# imu_68-v2.net
KiCad netlist of a schematic drawn in EAGLE
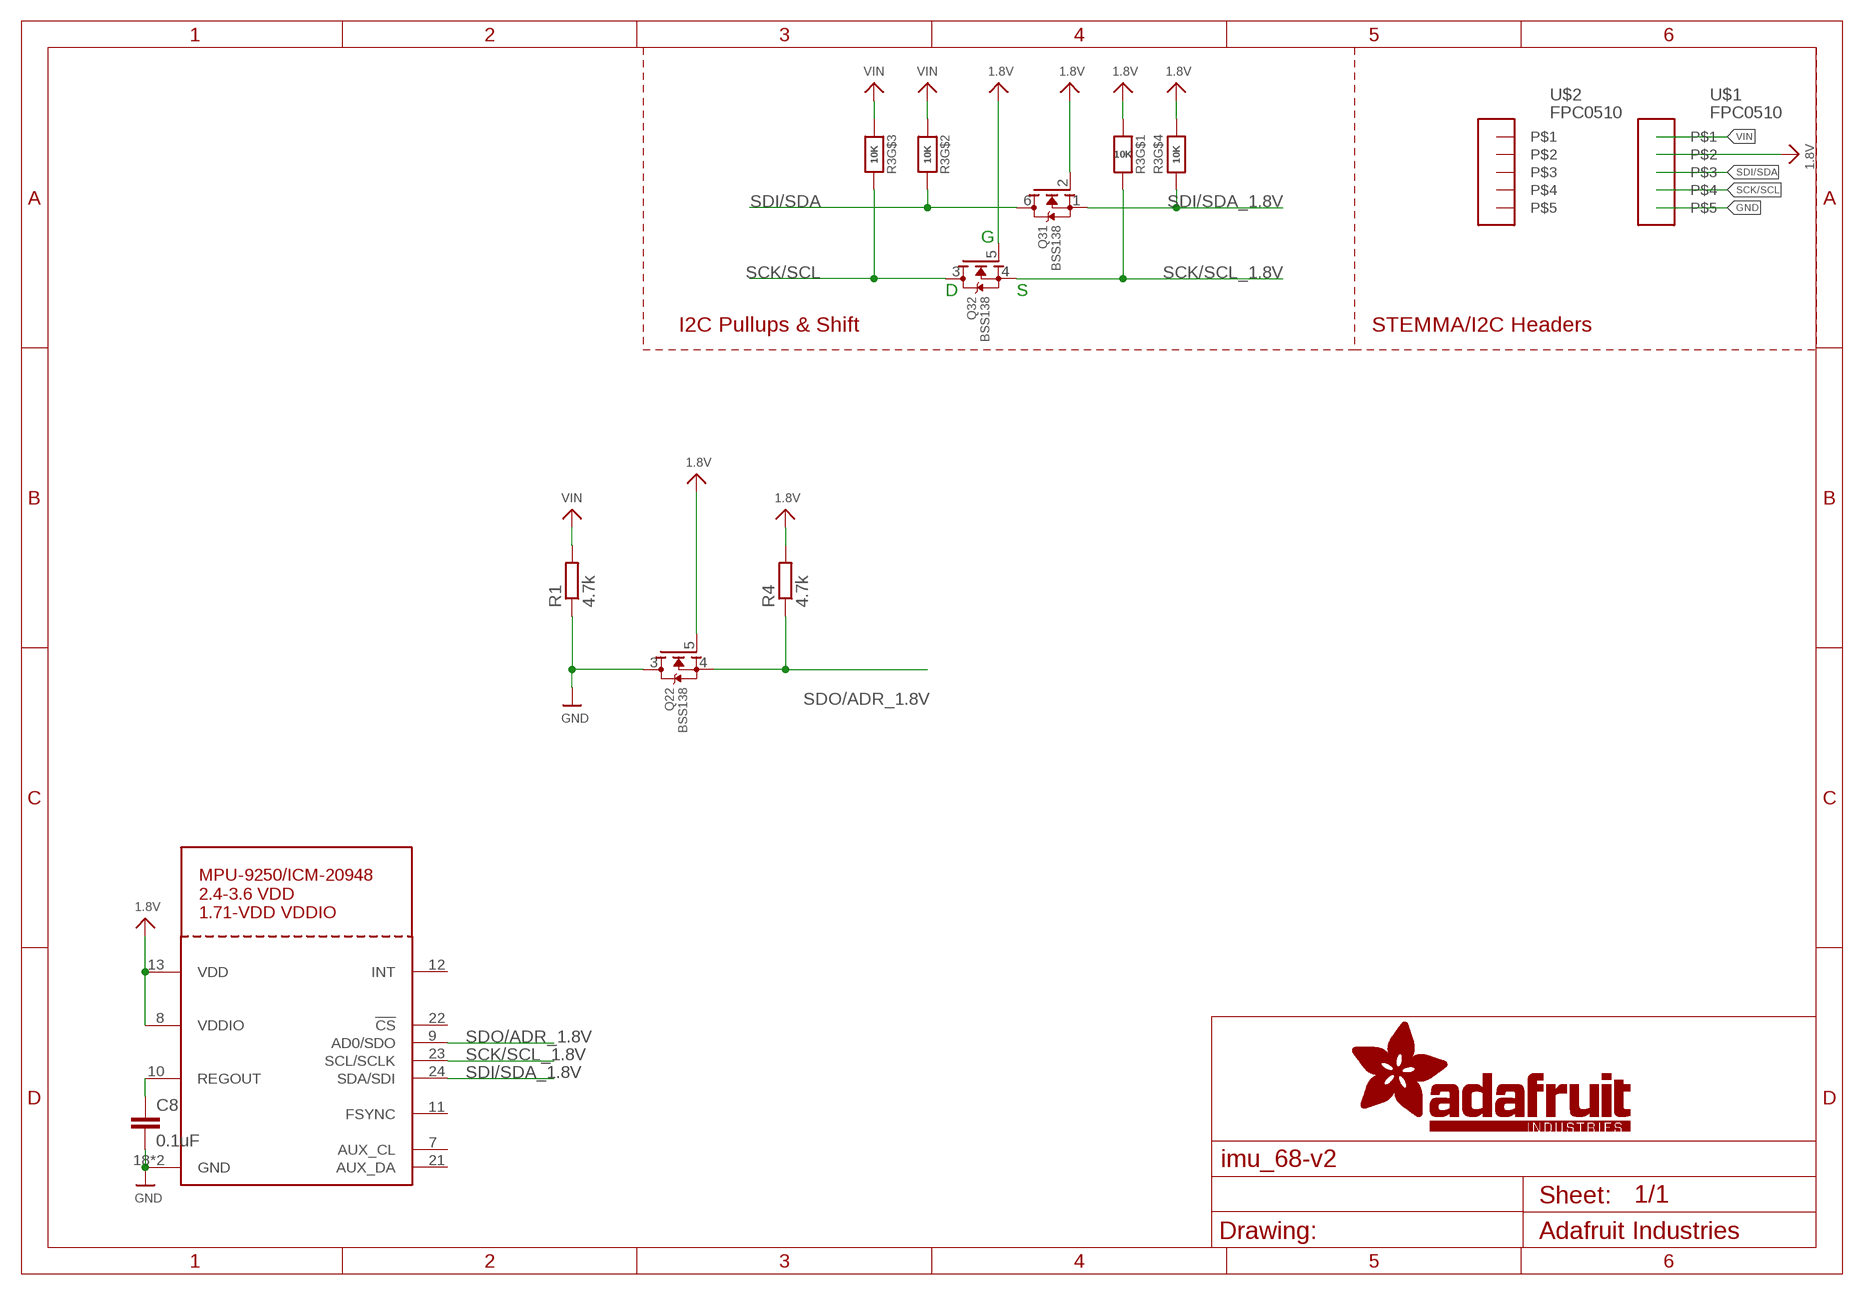
[diagram p0: schematic, sheet 1]

(export (version "E")
  (design (tool "Eeschema 10.0.6"))
  (components
    (comp (ref "C8")
      (value "0.1uF")
      (footprint "eagle-import:C0201")
      (libsource (lib "eagle-import") (part "C-EUC0201"))
    )
    (comp (ref "Q2")
      (value "BSS138")
      (footprint "eagle-import:SOT363")
      (libsource (lib "eagle-import") (part "MOSFET-N_DUAL"))
    )
    (comp (ref "Q3")
      (value "BSS138")
      (footprint "eagle-import:SOT363")
      (libsource (lib "eagle-import") (part "MOSFET-N_DUAL"))
    )
    (comp (ref "R1")
      (value "4.7k")
      (footprint "eagle-import:R0402")
      (libsource (lib "eagle-import") (part "R-EU_R0402"))
    )
    (comp (ref "R3")
      (value "10K")
      (footprint "eagle-import:RESPACK_4X0603")
      (libsource (lib "eagle-import") (part "RESISTOR_4PACK"))
    )
    (comp (ref "R4")
      (value "4.7k")
      (footprint "eagle-import:R0402")
      (libsource (lib "eagle-import") (part "R-EU_R0402"))
    )
    (comp (ref "U$1")
      (value "FPC0510")
      (footprint "eagle-import:FPC0510")
      (libsource (lib "eagle-import") (part "FPC0510"))
    )
    (comp (ref "U$2")
      (value "FPC0510")
      (footprint "eagle-import:FPC0510")
      (libsource (lib "eagle-import") (part "FPC0510"))
    )
    (comp (ref "U$21")
      (value "MPU-9250_ICM20948")
      (footprint "eagle-import:QFN24_3MM_NOEP")
      (libsource (lib "eagle-import") (part "MPU-9250_ICM20948"))
    )
  )
  (nets
    (net (code "1") (name "/SCK{slash}SCL_1.8V") (class "Default")
      (node (ref "Q3") (pin "4") (pinfunction "S_4") (pintype "bidirectional"))
      (node (ref "R3") (pin "1") (pinfunction "1_1") (pintype "passive"))
      (node (ref "U$21") (pin "23") (pinfunction "SCL/SCLK_23") (pintype "bidirectional"))
    )
    (net (code "2") (name "/SDI{slash}SDA_1.8V") (class "Default")
      (node (ref "Q3") (pin "1") (pinfunction "S_1") (pintype "bidirectional"))
      (node (ref "R3") (pin "5") (pinfunction "2_5") (pintype "passive"))
      (node (ref "U$21") (pin "24") (pinfunction "SDA/SDI_24") (pintype "bidirectional"))
    )
    (net (code "3") (name "/SDO{slash}ADR_1.8V") (class "Default")
      (node (ref "Q2") (pin "4") (pinfunction "S_4") (pintype "bidirectional"))
      (node (ref "R4") (pin "1") (pinfunction "1_1") (pintype "passive"))
      (node (ref "U$21") (pin "9") (pinfunction "AD0/SDO_9") (pintype "bidirectional"))
    )
    (net (code "4") (name "1.8V") (class "Default")
      (node (ref "Q2") (pin "5") (pinfunction "G_5") (pintype "bidirectional"))
      (node (ref "Q3") (pin "2") (pinfunction "G_2") (pintype "bidirectional"))
      (node (ref "Q3") (pin "5") (pinfunction "G_5") (pintype "bidirectional"))
      (node (ref "R3") (pin "4") (pinfunction "1_4") (pintype "passive"))
      (node (ref "R3") (pin "8") (pinfunction "2_8") (pintype "passive"))
      (node (ref "R4") (pin "2") (pinfunction "2_2") (pintype "passive"))
      (node (ref "U$1") (pin "P$2") (pinfunction "P$2_P$2") (pintype "bidirectional"))
      (node (ref "U$21") (pin "13") (pinfunction "VDD_13") (pintype "bidirectional"))
      (node (ref "U$21") (pin "8") (pinfunction "VDDIO_8") (pintype "bidirectional"))
    )
    (net (code "5") (name "GND") (class "Default")
      (node (ref "C8") (pin "2") (pinfunction "2_2") (pintype "passive"))
      (node (ref "Q2") (pin "3") (pinfunction "D_3") (pintype "bidirectional"))
      (node (ref "R1") (pin "1") (pinfunction "1_1") (pintype "passive"))
      (node (ref "U$1") (pin "P$5") (pinfunction "P$5_P$5") (pintype "bidirectional"))
      (node (ref "U$21") (pin "18") (pinfunction "GND_18") (pintype "bidirectional"))
      (node (ref "U$21") (pin "20") (pinfunction "GND_20") (pintype "bidirectional"))
    )
    (net (code "6") (name "Net-(U$21-REGOUT)") (class "Default")
      (node (ref "C8") (pin "1") (pinfunction "1_1") (pintype "passive"))
      (node (ref "U$21") (pin "10") (pinfunction "REGOUT_10") (pintype "bidirectional"))
    )
    (net (code "7") (name "SCK{slash}SCL") (class "Default")
      (node (ref "Q3") (pin "3") (pinfunction "D_3") (pintype "bidirectional"))
      (node (ref "R3") (pin "6") (pinfunction "2_6") (pintype "passive"))
      (node (ref "U$1") (pin "P$4") (pinfunction "P$4_P$4") (pintype "bidirectional"))
    )
    (net (code "8") (name "SDI{slash}SDA") (class "Default")
      (node (ref "Q3") (pin "6") (pinfunction "D_6") (pintype "bidirectional"))
      (node (ref "R3") (pin "7") (pinfunction "2_7") (pintype "passive"))
      (node (ref "U$1") (pin "P$3") (pinfunction "P$3_P$3") (pintype "bidirectional"))
    )
    (net (code "9") (name "VIN") (class "Default")
      (node (ref "R1") (pin "2") (pinfunction "2_2") (pintype "passive"))
      (node (ref "R3") (pin "2") (pinfunction "1_2") (pintype "passive"))
      (node (ref "R3") (pin "3") (pinfunction "1_3") (pintype "passive"))
      (node (ref "U$1") (pin "P$1") (pinfunction "P$1_P$1") (pintype "bidirectional"))
    )
    (net (code "10") (name "unconnected-(U$2-PadP$1)") (class "Default")
      (node (ref "U$2") (pin "P$1") (pinfunction "P$1_P$1") (pintype "bidirectional"))
    )
    (net (code "11") (name "unconnected-(U$2-PadP$2)") (class "Default")
      (node (ref "U$2") (pin "P$2") (pinfunction "P$2_P$2") (pintype "bidirectional"))
    )
    (net (code "12") (name "unconnected-(U$2-PadP$3)") (class "Default")
      (node (ref "U$2") (pin "P$3") (pinfunction "P$3_P$3") (pintype "bidirectional"))
    )
    (net (code "13") (name "unconnected-(U$2-PadP$4)") (class "Default")
      (node (ref "U$2") (pin "P$4") (pinfunction "P$4_P$4") (pintype "bidirectional"))
    )
    (net (code "14") (name "unconnected-(U$2-PadP$5)") (class "Default")
      (node (ref "U$2") (pin "P$5") (pinfunction "P$5_P$5") (pintype "bidirectional"))
    )
    (net (code "15") (name "unconnected-(U$21-AUX_CL-Pad7)") (class "Default")
      (node (ref "U$21") (pin "7") (pinfunction "AUX_CL_7") (pintype "bidirectional"))
    )
    (net (code "16") (name "unconnected-(U$21-AUX_DA-Pad21)") (class "Default")
      (node (ref "U$21") (pin "21") (pinfunction "AUX_DA_21") (pintype "bidirectional"))
    )
    (net (code "17") (name "unconnected-(U$21-FSYNC-Pad11)") (class "Default")
      (node (ref "U$21") (pin "11") (pinfunction "FSYNC_11") (pintype "bidirectional"))
    )
    (net (code "18") (name "unconnected-(U$21-INT-Pad12)") (class "Default")
      (node (ref "U$21") (pin "12") (pinfunction "INT_12") (pintype "bidirectional"))
    )
    (net (code "19") (name "unconnected-(U$21-~{CS}-Pad22)") (class "Default")
      (node (ref "U$21") (pin "22") (pinfunction "~{CS}_22") (pintype "bidirectional"))
    )
  )
)
